# raspiblitz-barracuda-connections.net
KiCad netlist of a schematic drawn in EasyEDA Pro
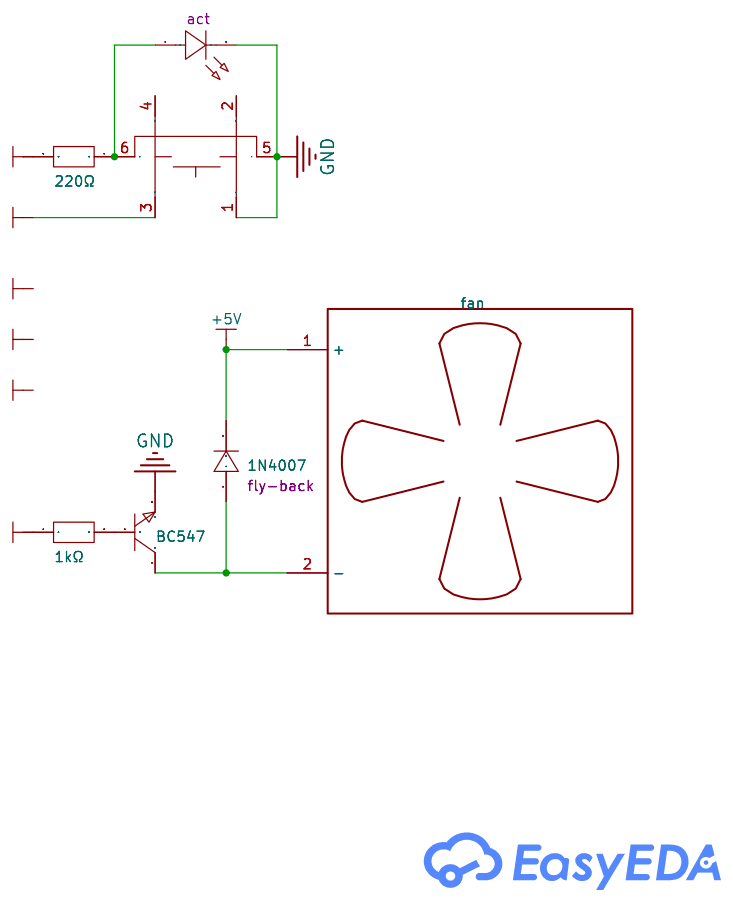
[diagram p0: schematic sheet]

(export (version "E")
  (design (tool "Eeschema 10.0.6"))
  (components
    (comp (ref "D1")
      (value "1N4007")
      (footprint "easyedapro:DO-41_BD2.4-L4.7-P8.70-D0.9-RD")
      (fields (field (name "Manufacturer") "MDD(辰达半导体)") (field (name "Comment") "fly-back"))
      (libsource (lib "easyedapro") (part "1N4007_C2457"))
    )
    (comp (ref "LED1")
      (value "TZ-L2-03YYBY2YDJ30-001")
      (footprint "easyedapro:LED-TH_BD3.0-P2.54-FD_YELLOW")
      (fields (field (name "Manufacturer") "TUOZHAN(拓展光电)") (field (name "Comment") "act"))
      (libsource (lib "easyedapro") (part "TZ-L2-03YYBY2YDJ30-001"))
    )
    (comp (ref "Q1")
      (value "BC547")
      (footprint "easyedapro:TO-92-3_L4.9-W3.7-P1.27-L")
      (fields (field (name "Manufacturer") "LGE(鲁光)"))
      (libsource (lib "easyedapro") (part "BC547B"))
    )
    (comp (ref "R1")
      (value "1kΩ")
      (footprint "easyedapro:RES-TH_BD2.7-L6.2-P10.20-D0.4")
      (fields (field (name "Manufacturer Part") "MF1/4W-1K±1%-ST52") (field (name "Manufacturer") "VO(翔胜)"))
      (libsource (lib "easyedapro") (part "MF1/4W-1K±1%-ST52"))
    )
    (comp (ref "R2")
      (value "220Ω")
      (footprint "easyedapro:RES-TH_BD2.7-L6.2-P10.20-D0.4")
      (fields (field (name "Manufacturer Part") "MF1/4W-220Ω±1% T") (field (name "Manufacturer") "CCO(千志电子)"))
      (libsource (lib "easyedapro") (part "MF1/4W-1K±1%-ST52"))
    )
    (comp (ref "SW1")
      (value "TM-001-D2-04")
      (footprint "easyedapro:SW-TH_TM-001-D2-04")
      (fields (field (name "Manufacturer") "XKB Connection(中国星坤)"))
      (libsource (lib "easyedapro") (part "TM-001-D2-04"))
    )
    (comp (ref "U2")
      (value "fan")
      (fields (field (name "Manufacturer Part") "?") (field (name "Contributor") "novasilisko"))
      (libsource (lib "easyedapro") (part "fan"))
    )
  )
  (nets
    (net (code "1") (name "+5V") (class "Default")
      (node (ref "D1") (pin "1") (pinfunction "C_1") (pintype "unspecified"))
      (node (ref "U2") (pin "1") (pinfunction "+_1") (pintype "unspecified"))
    )
    (net (code "2") (name "GND") (class "Default")
      (node (ref "LED1") (pin "2") (pinfunction "K_2") (pintype "unspecified"))
      (node (ref "Q1") (pin "3") (pinfunction "E_3") (pintype "input"))
      (node (ref "SW1") (pin "1") (pinfunction "1_1") (pintype "unspecified"))
      (node (ref "SW1") (pin "5") (pinfunction "-_5") (pintype "unspecified"))
    )
    (net (code "4") (name "GPIO3") (class "Default")
      (node (ref "SW1") (pin "3") (pinfunction "3_3") (pintype "unspecified"))
    )
    (net (code "6") (name "GPIO14") (class "Default")
      (node (ref "R1") (pin "1") (pinfunction "1_1") (pintype "unspecified"))
    )
    (net (code "7") (name "GPIO16") (class "Default")
      (node (ref "R2") (pin "2") (pinfunction "2_2") (pintype "unspecified"))
    )
    (net (code "9") (name "Net-(D1-A)") (class "Default")
      (node (ref "D1") (pin "2") (pinfunction "A_2") (pintype "unspecified"))
      (node (ref "Q1") (pin "1") (pinfunction "C_1") (pintype "input"))
      (node (ref "U2") (pin "2") (pinfunction "-_2") (pintype "unspecified"))
    )
    (net (code "10") (name "Net-(LED1-A)") (class "Default")
      (node (ref "LED1") (pin "1") (pinfunction "A_1") (pintype "unspecified"))
      (node (ref "R2") (pin "1") (pinfunction "1_1") (pintype "unspecified"))
      (node (ref "SW1") (pin "6") (pinfunction "+_6") (pintype "unspecified"))
    )
    (net (code "11") (name "Net-(Q1-B)") (class "Default")
      (node (ref "Q1") (pin "2") (pinfunction "B_2") (pintype "input"))
      (node (ref "R1") (pin "2") (pinfunction "2_2") (pintype "unspecified"))
    )
    (net (code "12") (name "unconnected-(SW1-Pad2)") (class "Default")
      (node (ref "SW1") (pin "2") (pinfunction "2_2") (pintype "unspecified"))
    )
    (net (code "13") (name "unconnected-(SW1-Pad4)") (class "Default")
      (node (ref "SW1") (pin "4") (pinfunction "4_4") (pintype "unspecified"))
    )
  )
)
